# SW_PDA_DPNOx5.net
KiCad netlist of a schematic drawn in Altium Designer
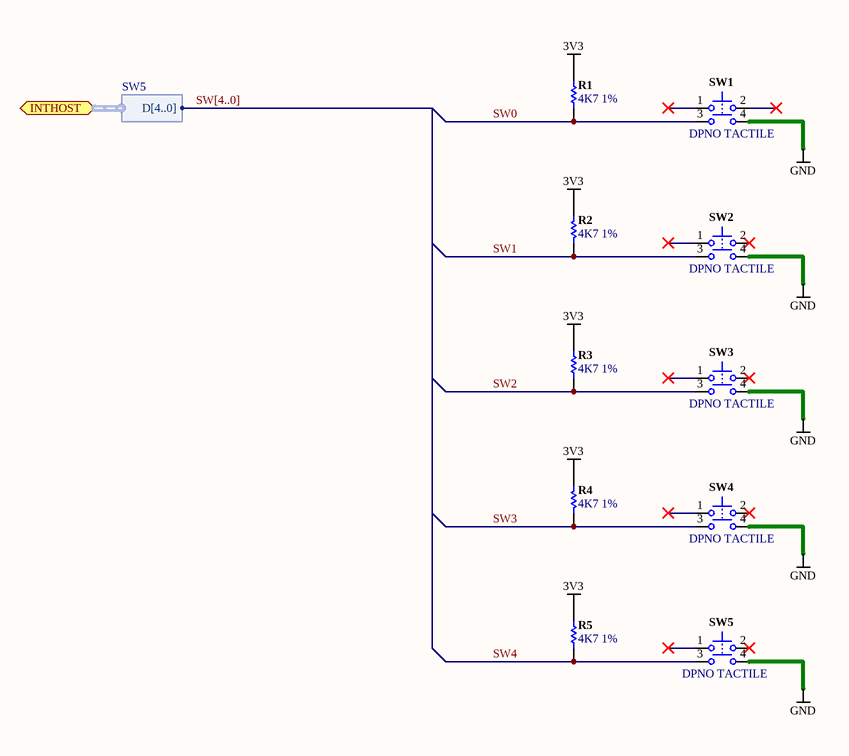
[diagram p0: SW_PDA_DPNOx5.SCHDOC]

(export (version "E")
  (design (tool "Eeschema 10.0.6"))
  (components
    (comp (ref "R1")
      (value "4K7 1%")
      (footprint "RESC1005-STAR")
      (description "Resistor, 4K7 1% 0402 (1005)")
      (fields (field (name "TOLERANCE") "1 %"))
      (libsource (lib "altium-import") (part "root_0_RES_"))
    )
    (comp (ref "R2")
      (value "4K7 1%")
      (footprint "RESC1005-STAR")
      (description "Resistor, 4K7 1% 0402 (1005)")
      (fields (field (name "TOLERANCE") "1 %"))
      (libsource (lib "altium-import") (part "root_0_mirrored_RES_"))
    )
    (comp (ref "R3")
      (value "4K7 1%")
      (footprint "RESC1005-STAR")
      (description "Resistor, 4K7 1% 0402 (1005)")
      (fields (field (name "TOLERANCE") "1 %"))
      (libsource (lib "altium-import") (part "root_2_RES_"))
    )
    (comp (ref "R4")
      (value "4K7 1%")
      (footprint "RESC1005-STAR")
      (description "Resistor, 4K7 1% 0402 (1005)")
      (fields (field (name "TOLERANCE") "1 %"))
      (libsource (lib "altium-import") (part "root_0_mirrored_RES_"))
    )
    (comp (ref "R5")
      (value "4K7 1%")
      (footprint "RESC1005-STAR")
      (description "Resistor, 4K7 1% 0402 (1005)")
      (fields (field (name "TOLERANCE") "1 %"))
      (libsource (lib "altium-import") (part "root_2_RES_"))
    )
    (comp (ref "SW1")
      (value "DPNO TACTILE")
      (footprint "IT-2175")
      (description "Switch, DPNO Push Button Through-Hole")
      (libsource (lib "altium-import") (part "root_0_SWI-PB-DPNO_"))
    )
    (comp (ref "SW2")
      (value "DPNO TACTILE")
      (footprint "IT-2175")
      (description "Switch, DPNO Push Button Through-Hole")
      (libsource (lib "altium-import") (part "root_0_SWI-PB-DPNO_"))
    )
    (comp (ref "SW3")
      (value "DPNO TACTILE")
      (footprint "IT-2175")
      (description "Switch, DPNO Push Button Through-Hole")
      (libsource (lib "altium-import") (part "root_0_SWI-PB-DPNO_"))
    )
    (comp (ref "SW4")
      (value "DPNO TACTILE")
      (footprint "IT-2175")
      (description "Switch, DPNO Push Button Through-Hole")
      (libsource (lib "altium-import") (part "root_0_SWI-PB-DPNO_"))
    )
    (comp (ref "SW5")
      (value "DPNO TACTILE")
      (footprint "IT-2175")
      (description "Switch, DPNO Push Button Through-Hole")
      (libsource (lib "altium-import") (part "root_0_SWI-PB-DPNO_"))
    )
  )
  (nets
    (net (code "2") (name "/SW0") (class "Default")
      (node (ref "R1") (pin "2") (pinfunction "2_2") (pintype "passive"))
      (node (ref "SW1") (pin "3") (pinfunction "3_3") (pintype "passive"))
    )
    (net (code "3") (name "/SW1") (class "Default")
      (node (ref "R2") (pin "2") (pinfunction "2_2") (pintype "passive"))
      (node (ref "SW2") (pin "3") (pinfunction "3_3") (pintype "passive"))
    )
    (net (code "4") (name "/SW2") (class "Default")
      (node (ref "R3") (pin "1") (pinfunction "1_1") (pintype "passive"))
      (node (ref "SW3") (pin "3") (pinfunction "3_3") (pintype "passive"))
    )
    (net (code "5") (name "/SW3") (class "Default")
      (node (ref "R4") (pin "2") (pinfunction "2_2") (pintype "passive"))
      (node (ref "SW4") (pin "3") (pinfunction "3_3") (pintype "passive"))
    )
    (net (code "6") (name "/SW4") (class "Default")
      (node (ref "R5") (pin "1") (pinfunction "1_1") (pintype "passive"))
      (node (ref "SW5") (pin "3") (pinfunction "3_3") (pintype "passive"))
    )
    (net (code "9") (name "3V3") (class "Default")
      (node (ref "R1") (pin "1") (pinfunction "1_1") (pintype "passive"))
      (node (ref "R2") (pin "1") (pinfunction "1_1") (pintype "passive"))
      (node (ref "R3") (pin "2") (pinfunction "2_2") (pintype "passive"))
      (node (ref "R4") (pin "1") (pinfunction "1_1") (pintype "passive"))
      (node (ref "R5") (pin "2") (pinfunction "2_2") (pintype "passive"))
    )
    (net (code "10") (name "GND") (class "Default")
      (node (ref "SW1") (pin "4") (pinfunction "4_4") (pintype "passive"))
      (node (ref "SW2") (pin "4") (pinfunction "4_4") (pintype "passive"))
      (node (ref "SW3") (pin "4") (pinfunction "4_4") (pintype "passive"))
      (node (ref "SW4") (pin "4") (pinfunction "4_4") (pintype "passive"))
      (node (ref "SW5") (pin "4") (pinfunction "4_4") (pintype "passive"))
    )
    (net (code "11") (name "unconnected-(SW1-Pad1)") (class "Default")
      (node (ref "SW1") (pin "1") (pinfunction "1_1") (pintype "passive+no_connect"))
    )
    (net (code "12") (name "unconnected-(SW1-Pad2)") (class "Default")
      (node (ref "SW1") (pin "2") (pinfunction "2_2") (pintype "passive+no_connect"))
    )
    (net (code "13") (name "unconnected-(SW2-Pad1)") (class "Default")
      (node (ref "SW2") (pin "1") (pinfunction "1_1") (pintype "passive+no_connect"))
    )
    (net (code "14") (name "unconnected-(SW2-Pad2)") (class "Default")
      (node (ref "SW2") (pin "2") (pinfunction "2_2") (pintype "passive+no_connect"))
    )
    (net (code "15") (name "unconnected-(SW3-Pad1)") (class "Default")
      (node (ref "SW3") (pin "1") (pinfunction "1_1") (pintype "passive+no_connect"))
    )
    (net (code "16") (name "unconnected-(SW3-Pad2)") (class "Default")
      (node (ref "SW3") (pin "2") (pinfunction "2_2") (pintype "passive+no_connect"))
    )
    (net (code "17") (name "unconnected-(SW4-Pad1)") (class "Default")
      (node (ref "SW4") (pin "1") (pinfunction "1_1") (pintype "passive+no_connect"))
    )
    (net (code "18") (name "unconnected-(SW4-Pad2)") (class "Default")
      (node (ref "SW4") (pin "2") (pinfunction "2_2") (pintype "passive+no_connect"))
    )
    (net (code "19") (name "unconnected-(SW5-Pad1)") (class "Default")
      (node (ref "SW5") (pin "1") (pinfunction "1_1") (pintype "passive+no_connect"))
    )
    (net (code "20") (name "unconnected-(SW5-Pad2)") (class "Default")
      (node (ref "SW5") (pin "2") (pinfunction "2_2") (pintype "passive+no_connect"))
    )
  )
)
